# Bypass_FPGA_1V2.net
KiCad netlist of a schematic drawn in Altium Designer
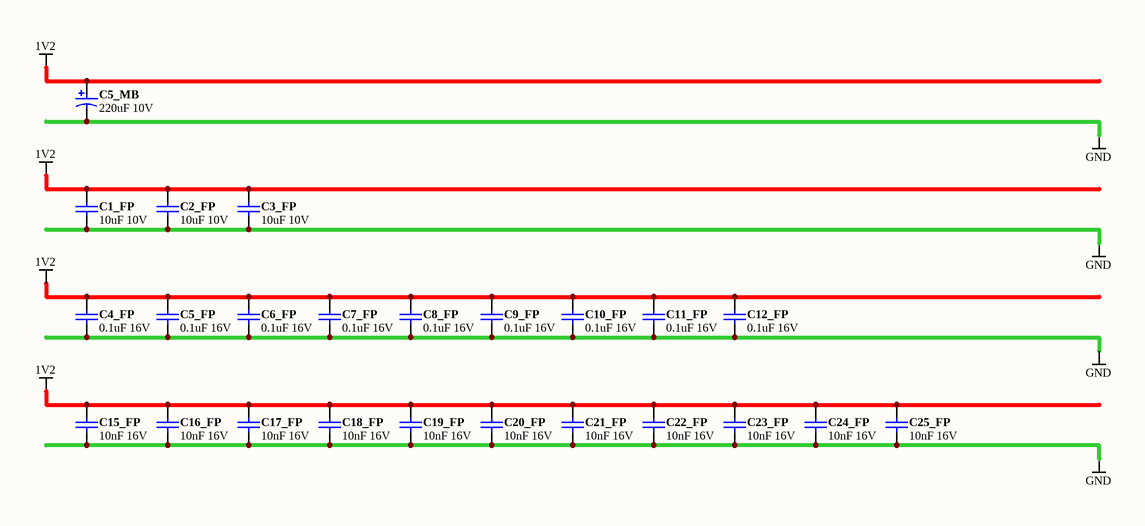
[diagram p0: Bypass_FPGA_1V2.SCHDOC]

(export (version "E")
  (design (tool "Eeschema 10.0.6"))
  (components
    (comp (ref "C1_FP")
      (value "10uF 10V")
      (footprint "CAPC2012-STAR")
      (description "Capacitor, Ceramic, 10uF 10% 10V 0805 (2012) X5R")
      (fields (field (name "TOLERANCE") "10 %"))
      (libsource (lib "AltiumDesignLibrary") (part "CAP-NP"))
    )
    (comp (ref "C2_FP")
      (value "10uF 10V")
      (footprint "CAPC2012-STAR")
      (description "Capacitor, Ceramic, 10uF 10% 10V 0805 (2012) X5R")
      (fields (field (name "TOLERANCE") "10 %"))
      (libsource (lib "AltiumDesignLibrary") (part "CAP-NP"))
    )
    (comp (ref "C3_FP")
      (value "10uF 10V")
      (footprint "CAPC2012-STAR")
      (description "Capacitor, Ceramic, 10uF 10% 10V 0805 (2012) X5R")
      (fields (field (name "TOLERANCE") "10 %"))
      (libsource (lib "AltiumDesignLibrary") (part "CAP-NP"))
    )
    (comp (ref "C4_FP")
      (value "0.1uF 16V")
      (footprint "CAPC1005-STAR")
      (description "Capacitor, Ceramic, 0.1uF 10% 16V 0402 (1005) X7R")
      (fields (field (name "TOLERANCE") "10 %"))
      (libsource (lib "AltiumDesignLibrary") (part "CAP-NP"))
    )
    (comp (ref "C5_FP")
      (value "0.1uF 16V")
      (footprint "CAPC1005-STAR")
      (description "Capacitor, Ceramic, 0.1uF 10% 16V 0402 (1005) X7R")
      (fields (field (name "TOLERANCE") "10 %"))
      (libsource (lib "AltiumDesignLibrary") (part "CAP-NP"))
    )
    (comp (ref "C5_MB")
      (value "220uF 10V")
      (footprint "CAPC7343-STAR")
      (description "Capacitor, Tantalum, 220uF 10% 10V MCCT-D (7343-31)")
      (fields (field (name "TOLERANCE") "10 %"))
      (libsource (lib "AltiumDesignLibrary") (part "CAP-P"))
    )
    (comp (ref "C6_FP")
      (value "0.1uF 16V")
      (footprint "CAPC1005-STAR")
      (description "Capacitor, Ceramic, 0.1uF 10% 16V 0402 (1005) X7R")
      (fields (field (name "TOLERANCE") "10 %"))
      (libsource (lib "AltiumDesignLibrary") (part "CAP-NP"))
    )
    (comp (ref "C7_FP")
      (value "0.1uF 16V")
      (footprint "CAPC1005-STAR")
      (description "Capacitor, Ceramic, 0.1uF 10% 16V 0402 (1005) X7R")
      (fields (field (name "TOLERANCE") "10 %"))
      (libsource (lib "AltiumDesignLibrary") (part "CAP-NP"))
    )
    (comp (ref "C8_FP")
      (value "0.1uF 16V")
      (footprint "CAPC1005-STAR")
      (description "Capacitor, Ceramic, 0.1uF 10% 16V 0402 (1005) X7R")
      (fields (field (name "TOLERANCE") "10 %"))
      (libsource (lib "AltiumDesignLibrary") (part "CAP-NP"))
    )
    (comp (ref "C9_FP")
      (value "0.1uF 16V")
      (footprint "CAPC1005-STAR")
      (description "Capacitor, Ceramic, 0.1uF 10% 16V 0402 (1005) X7R")
      (fields (field (name "TOLERANCE") "10 %"))
      (libsource (lib "AltiumDesignLibrary") (part "CAP-NP"))
    )
    (comp (ref "C10_FP")
      (value "0.1uF 16V")
      (footprint "CAPC1005-STAR")
      (description "Capacitor, Ceramic, 0.1uF 10% 16V 0402 (1005) X7R")
      (fields (field (name "TOLERANCE") "10 %"))
      (libsource (lib "AltiumDesignLibrary") (part "CAP-NP"))
    )
    (comp (ref "C11_FP")
      (value "0.1uF 16V")
      (footprint "CAPC1005-STAR")
      (description "Capacitor, Ceramic, 0.1uF 10% 16V 0402 (1005) X7R")
      (fields (field (name "TOLERANCE") "10 %"))
      (libsource (lib "AltiumDesignLibrary") (part "CAP-NP"))
    )
    (comp (ref "C12_FP")
      (value "0.1uF 16V")
      (footprint "CAPC1005-STAR")
      (description "Capacitor, Ceramic, 0.1uF 10% 16V 0402 (1005) X7R")
      (fields (field (name "TOLERANCE") "10 %"))
      (libsource (lib "AltiumDesignLibrary") (part "CAP-NP"))
    )
    (comp (ref "C15_FP")
      (value "10nF 16V")
      (footprint "CAPC1005-STAR")
      (description "Capacitor, Ceramic, 10nF 10% 16V 0402 (1005) X7R")
      (fields (field (name "TOLERANCE") "10 %"))
      (libsource (lib "AltiumDesignLibrary") (part "CAP-NP"))
    )
    (comp (ref "C16_FP")
      (value "10nF 16V")
      (footprint "CAPC1005-STAR")
      (description "Capacitor, Ceramic, 10nF 10% 16V 0402 (1005) X7R")
      (fields (field (name "TOLERANCE") "10 %"))
      (libsource (lib "AltiumDesignLibrary") (part "CAP-NP"))
    )
    (comp (ref "C17_FP")
      (value "10nF 16V")
      (footprint "CAPC1005-STAR")
      (description "Capacitor, Ceramic, 10nF 10% 16V 0402 (1005) X7R")
      (fields (field (name "TOLERANCE") "10 %"))
      (libsource (lib "AltiumDesignLibrary") (part "CAP-NP"))
    )
    (comp (ref "C18_FP")
      (value "10nF 16V")
      (footprint "CAPC1005-STAR")
      (description "Capacitor, Ceramic, 10nF 10% 16V 0402 (1005) X7R")
      (fields (field (name "TOLERANCE") "10 %"))
      (libsource (lib "AltiumDesignLibrary") (part "CAP-NP"))
    )
    (comp (ref "C19_FP")
      (value "10nF 16V")
      (footprint "CAPC1005-STAR")
      (description "Capacitor, Ceramic, 10nF 10% 16V 0402 (1005) X7R")
      (fields (field (name "TOLERANCE") "10 %"))
      (libsource (lib "AltiumDesignLibrary") (part "CAP-NP"))
    )
    (comp (ref "C20_FP")
      (value "10nF 16V")
      (footprint "CAPC1005-STAR")
      (description "Capacitor, Ceramic, 10nF 10% 16V 0402 (1005) X7R")
      (fields (field (name "TOLERANCE") "10 %"))
      (libsource (lib "AltiumDesignLibrary") (part "CAP-NP"))
    )
    (comp (ref "C21_FP")
      (value "10nF 16V")
      (footprint "CAPC1005-STAR")
      (description "Capacitor, Ceramic, 10nF 10% 16V 0402 (1005) X7R")
      (fields (field (name "TOLERANCE") "10 %"))
      (libsource (lib "AltiumDesignLibrary") (part "CAP-NP"))
    )
    (comp (ref "C22_FP")
      (value "10nF 16V")
      (footprint "CAPC1005-STAR")
      (description "Capacitor, Ceramic, 10nF 10% 16V 0402 (1005) X7R")
      (fields (field (name "TOLERANCE") "10 %"))
      (libsource (lib "AltiumDesignLibrary") (part "CAP-NP"))
    )
    (comp (ref "C23_FP")
      (value "10nF 16V")
      (footprint "CAPC1005-STAR")
      (description "Capacitor, Ceramic, 10nF 10% 16V 0402 (1005) X7R")
      (fields (field (name "TOLERANCE") "10 %"))
      (libsource (lib "AltiumDesignLibrary") (part "CAP-NP"))
    )
    (comp (ref "C24_FP")
      (value "10nF 16V")
      (footprint "CAPC1005-STAR")
      (description "Capacitor, Ceramic, 10nF 10% 16V 0402 (1005) X7R")
      (fields (field (name "TOLERANCE") "10 %"))
      (libsource (lib "AltiumDesignLibrary") (part "CAP-NP"))
    )
    (comp (ref "C25_FP")
      (value "10nF 16V")
      (footprint "CAPC1005-STAR")
      (description "Capacitor, Ceramic, 10nF 10% 16V 0402 (1005) X7R")
      (fields (field (name "TOLERANCE") "10 %"))
      (libsource (lib "AltiumDesignLibrary") (part "CAP-NP"))
    )
  )
  (nets
    (net (code "1") (name "1V2") (class "Default")
      (node (ref "C10_FP") (pin "1") (pinfunction "1_1") (pintype "passive"))
      (node (ref "C11_FP") (pin "1") (pinfunction "1_1") (pintype "passive"))
      (node (ref "C12_FP") (pin "1") (pinfunction "1_1") (pintype "passive"))
      (node (ref "C15_FP") (pin "1") (pinfunction "1_1") (pintype "passive"))
      (node (ref "C16_FP") (pin "1") (pinfunction "1_1") (pintype "passive"))
      (node (ref "C17_FP") (pin "1") (pinfunction "1_1") (pintype "passive"))
      (node (ref "C18_FP") (pin "1") (pinfunction "1_1") (pintype "passive"))
      (node (ref "C19_FP") (pin "1") (pinfunction "1_1") (pintype "passive"))
      (node (ref "C1_FP") (pin "1") (pinfunction "1_1") (pintype "passive"))
      (node (ref "C20_FP") (pin "1") (pinfunction "1_1") (pintype "passive"))
      (node (ref "C21_FP") (pin "1") (pinfunction "1_1") (pintype "passive"))
      (node (ref "C22_FP") (pin "1") (pinfunction "1_1") (pintype "passive"))
      (node (ref "C23_FP") (pin "1") (pinfunction "1_1") (pintype "passive"))
      (node (ref "C24_FP") (pin "1") (pinfunction "1_1") (pintype "passive"))
      (node (ref "C25_FP") (pin "1") (pinfunction "1_1") (pintype "passive"))
      (node (ref "C2_FP") (pin "1") (pinfunction "1_1") (pintype "passive"))
      (node (ref "C3_FP") (pin "1") (pinfunction "1_1") (pintype "passive"))
      (node (ref "C4_FP") (pin "1") (pinfunction "1_1") (pintype "passive"))
      (node (ref "C5_FP") (pin "1") (pinfunction "1_1") (pintype "passive"))
      (node (ref "C5_MB") (pin "1") (pinfunction "1_1") (pintype "passive"))
      (node (ref "C6_FP") (pin "1") (pinfunction "1_1") (pintype "passive"))
      (node (ref "C7_FP") (pin "1") (pinfunction "1_1") (pintype "passive"))
      (node (ref "C8_FP") (pin "1") (pinfunction "1_1") (pintype "passive"))
      (node (ref "C9_FP") (pin "1") (pinfunction "1_1") (pintype "passive"))
    )
    (net (code "2") (name "GND") (class "Default")
      (node (ref "C10_FP") (pin "2") (pinfunction "2_2") (pintype "passive"))
      (node (ref "C11_FP") (pin "2") (pinfunction "2_2") (pintype "passive"))
      (node (ref "C12_FP") (pin "2") (pinfunction "2_2") (pintype "passive"))
      (node (ref "C15_FP") (pin "2") (pinfunction "2_2") (pintype "passive"))
      (node (ref "C16_FP") (pin "2") (pinfunction "2_2") (pintype "passive"))
      (node (ref "C17_FP") (pin "2") (pinfunction "2_2") (pintype "passive"))
      (node (ref "C18_FP") (pin "2") (pinfunction "2_2") (pintype "passive"))
      (node (ref "C19_FP") (pin "2") (pinfunction "2_2") (pintype "passive"))
      (node (ref "C1_FP") (pin "2") (pinfunction "2_2") (pintype "passive"))
      (node (ref "C20_FP") (pin "2") (pinfunction "2_2") (pintype "passive"))
      (node (ref "C21_FP") (pin "2") (pinfunction "2_2") (pintype "passive"))
      (node (ref "C22_FP") (pin "2") (pinfunction "2_2") (pintype "passive"))
      (node (ref "C23_FP") (pin "2") (pinfunction "2_2") (pintype "passive"))
      (node (ref "C24_FP") (pin "2") (pinfunction "2_2") (pintype "passive"))
      (node (ref "C25_FP") (pin "2") (pinfunction "2_2") (pintype "passive"))
      (node (ref "C2_FP") (pin "2") (pinfunction "2_2") (pintype "passive"))
      (node (ref "C3_FP") (pin "2") (pinfunction "2_2") (pintype "passive"))
      (node (ref "C4_FP") (pin "2") (pinfunction "2_2") (pintype "passive"))
      (node (ref "C5_FP") (pin "2") (pinfunction "2_2") (pintype "passive"))
      (node (ref "C5_MB") (pin "2") (pinfunction "2_2") (pintype "passive"))
      (node (ref "C6_FP") (pin "2") (pinfunction "2_2") (pintype "passive"))
      (node (ref "C7_FP") (pin "2") (pinfunction "2_2") (pintype "passive"))
      (node (ref "C8_FP") (pin "2") (pinfunction "2_2") (pintype "passive"))
      (node (ref "C9_FP") (pin "2") (pinfunction "2_2") (pintype "passive"))
    )
  )
)
